# Squid_Leg_Controller.net
KiCad netlist of a schematic drawn in EAGLE
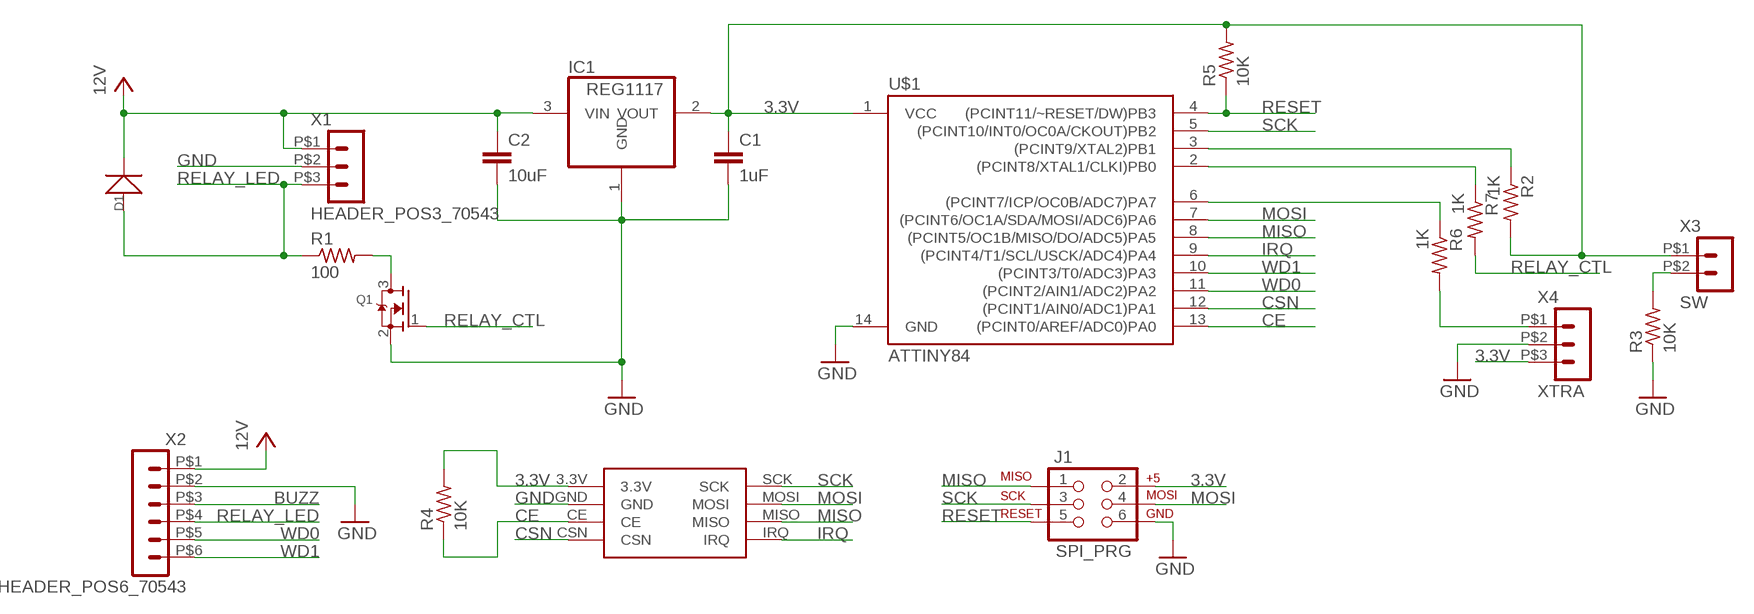
[diagram p0: schematic, sheet 1]

(export (version "E")
  (design (tool "Eeschema 10.0.6"))
  (components
    (comp (ref "C1")
      (value "1uF")
      (footprint "eagle-import:0805")
      (libsource (lib "eagle-import") (part "CAP0805"))
    )
    (comp (ref "C2")
      (value "10uF")
      (footprint "eagle-import:1206")
      (libsource (lib "eagle-import") (part "CAP1206"))
    )
    (comp (ref "D1")
      (value "D-SMA")
      (footprint "eagle-import:DO-214AC")
      (libsource (lib "eagle-import") (part "D-SMA"))
    )
    (comp (ref "IC1")
      (value "REG1117")
      (footprint "eagle-import:SOT223")
      (libsource (lib "eagle-import") (part "REG1117"))
    )
    (comp (ref "J1")
      (value "SPI_PRG")
      (footprint "eagle-import:2X3_LOCK")
      (libsource (lib "eagle-import") (part "AVR_SPI_PRG_62X3_LOCK"))
    )
    (comp (ref "Q1")
      (value "MOSFET-NREFLOW")
      (footprint "eagle-import:SOT23")
      (libsource (lib "eagle-import") (part "MOSFET-NREFLOW"))
    )
    (comp (ref "R1")
      (value "100")
      (footprint "eagle-import:R0603")
      (libsource (lib "eagle-import") (part "R-US_R0603"))
    )
    (comp (ref "R2")
      (value "1K")
      (footprint "eagle-import:R0603")
      (libsource (lib "eagle-import") (part "R-US_R0603"))
    )
    (comp (ref "R3")
      (value "10K")
      (footprint "eagle-import:R0603")
      (libsource (lib "eagle-import") (part "R-US_R0603"))
    )
    (comp (ref "R4")
      (value "10K")
      (footprint "eagle-import:R0603")
      (libsource (lib "eagle-import") (part "R-US_R0603"))
    )
    (comp (ref "R5")
      (value "10K")
      (footprint "eagle-import:R0603")
      (libsource (lib "eagle-import") (part "R-US_R0603"))
    )
    (comp (ref "R6")
      (value "1K")
      (footprint "eagle-import:R0603")
      (libsource (lib "eagle-import") (part "R-US_R0603"))
    )
    (comp (ref "R7")
      (value "1K")
      (footprint "eagle-import:R0603")
      (libsource (lib "eagle-import") (part "R-US_R0603"))
    )
    (comp (ref "U$1")
      (value "ATTINY84")
      (footprint "eagle-import:SO14")
      (libsource (lib "eagle-import") (part "ATTINY84"))
    )
    (comp (ref "U$4")
      (value "NRF24L01+")
      (footprint "eagle-import:NRF24L01+_MODULE_OFFBRD")
      (libsource (lib "eagle-import") (part "NRF24L01+_MODULEOFF_BOARD"))
    )
    (comp (ref "X1")
      (value "HEADER_POS3_70543")
      (footprint "eagle-import:70543-POS3")
      (libsource (lib "eagle-import") (part "HEADER_POS3_?70543"))
    )
    (comp (ref "X2")
      (value "HEADER_POS6_70543")
      (footprint "eagle-import:70543-POS6")
      (libsource (lib "eagle-import") (part "HEADER_POS6_?70543"))
    )
    (comp (ref "X3")
      (value "SW")
      (footprint "eagle-import:70543-POS2")
      (libsource (lib "eagle-import") (part "HEADER_POS2_?70543"))
    )
    (comp (ref "X4")
      (value "XTRA")
      (footprint "eagle-import:70543-POS3")
      (libsource (lib "eagle-import") (part "HEADER_POS3_?70543"))
    )
  )
  (nets
    (net (code "1") (name "/3.3V") (class "Default")
      (node (ref "C1") (pin "1") (pinfunction "1_1") (pintype "passive"))
      (node (ref "IC1") (pin "2") (pinfunction "VOUT_2") (pintype "output"))
      (node (ref "J1") (pin "2") (pinfunction "2_2") (pintype "passive"))
      (node (ref "R2") (pin "2") (pinfunction "2_2") (pintype "passive"))
      (node (ref "R4") (pin "2") (pinfunction "2_2") (pintype "passive"))
      (node (ref "R5") (pin "2") (pinfunction "2_2") (pintype "passive"))
      (node (ref "U$1") (pin "1") (pinfunction "VCC_1") (pintype "bidirectional"))
      (node (ref "U$4") (pin "3.3V") (pinfunction "3.3V_3.3V") (pintype "bidirectional"))
      (node (ref "X3") (pin "P$1") (pinfunction "1_P$1") (pintype "passive"))
      (node (ref "X4") (pin "P$3") (pinfunction "3_P$3") (pintype "passive"))
    )
    (net (code "2") (name "/BUZZ") (class "Default")
      (node (ref "X2") (pin "P$3") (pinfunction "3_P$3") (pintype "passive"))
    )
    (net (code "3") (name "/CE") (class "Default")
      (node (ref "R4") (pin "1") (pinfunction "1_1") (pintype "passive"))
      (node (ref "U$1") (pin "13") (pinfunction "(PCINT0/AREF/ADC0)PA0_13") (pintype "bidirectional"))
      (node (ref "U$4") (pin "CE") (pinfunction "CE_CE") (pintype "bidirectional"))
    )
    (net (code "4") (name "/CSN") (class "Default")
      (node (ref "U$1") (pin "12") (pinfunction "(PCINT1/AIN0/ADC1)PA1_12") (pintype "bidirectional"))
      (node (ref "U$4") (pin "CSN") (pinfunction "CSN_CSN") (pintype "bidirectional"))
    )
    (net (code "5") (name "/IRQ") (class "Default")
      (node (ref "U$1") (pin "9") (pinfunction "(PCINT4/T1/SCL/USCK/ADC4)PA4_9") (pintype "bidirectional"))
      (node (ref "U$4") (pin "IRQ") (pinfunction "IRQ_IRQ") (pintype "bidirectional"))
    )
    (net (code "6") (name "/MISO") (class "Default")
      (node (ref "J1") (pin "1") (pinfunction "1_1") (pintype "passive"))
      (node (ref "U$1") (pin "8") (pinfunction "(PCINT5/OC1B/MISO/DO/ADC5)PA5_8") (pintype "bidirectional"))
      (node (ref "U$4") (pin "MISO") (pinfunction "MISO_MISO") (pintype "bidirectional"))
    )
    (net (code "7") (name "/MOSI") (class "Default")
      (node (ref "J1") (pin "4") (pinfunction "4_4") (pintype "passive"))
      (node (ref "U$1") (pin "7") (pinfunction "(PCINT6/OC1A/SDA/MOSI/ADC6)PA6_7") (pintype "bidirectional"))
      (node (ref "U$4") (pin "MOSI") (pinfunction "MOSI_MOSI") (pintype "bidirectional"))
    )
    (net (code "8") (name "/RELAY_CTL") (class "Default")
      (node (ref "Q1") (pin "1") (pinfunction "G_1") (pintype "bidirectional"))
      (node (ref "R7") (pin "2") (pinfunction "2_2") (pintype "passive"))
    )
    (net (code "9") (name "/RELAY_LED") (class "Default")
      (node (ref "D1") (pin "1") (pinfunction "+_1") (pintype "passive"))
      (node (ref "R1") (pin "1") (pinfunction "1_1") (pintype "passive"))
      (node (ref "X1") (pin "P$3") (pinfunction "3_P$3") (pintype "passive"))
      (node (ref "X2") (pin "P$4") (pinfunction "4_P$4") (pintype "passive"))
    )
    (net (code "10") (name "/RESET") (class "Default")
      (node (ref "J1") (pin "5") (pinfunction "5_5") (pintype "passive"))
      (node (ref "R5") (pin "1") (pinfunction "1_1") (pintype "passive"))
      (node (ref "U$1") (pin "4") (pinfunction "(PCINT11/~{RESET/DW})PB3_4") (pintype "bidirectional"))
    )
    (net (code "11") (name "/SCK") (class "Default")
      (node (ref "J1") (pin "3") (pinfunction "3_3") (pintype "passive"))
      (node (ref "U$1") (pin "5") (pinfunction "(PCINT10/INT0/OC0A/CKOUT)PB2_5") (pintype "bidirectional"))
      (node (ref "U$4") (pin "SCK") (pinfunction "SCK_SCK") (pintype "bidirectional"))
    )
    (net (code "12") (name "/WD0") (class "Default")
      (node (ref "U$1") (pin "11") (pinfunction "(PCINT2/AIN1/ADC2)PA2_11") (pintype "bidirectional"))
      (node (ref "X2") (pin "P$5") (pinfunction "5_P$5") (pintype "passive"))
    )
    (net (code "13") (name "/WD1") (class "Default")
      (node (ref "U$1") (pin "10") (pinfunction "(PCINT3/T0/ADC3)PA3_10") (pintype "bidirectional"))
      (node (ref "X2") (pin "P$6") (pinfunction "6_P$6") (pintype "passive"))
    )
    (net (code "14") (name "12V") (class "Default")
      (node (ref "C2") (pin "1") (pinfunction "1_1") (pintype "passive"))
      (node (ref "D1") (pin "2") (pinfunction "-_2") (pintype "passive"))
      (node (ref "IC1") (pin "3") (pinfunction "VIN_3") (pintype "input"))
      (node (ref "X1") (pin "P$1") (pinfunction "1_P$1") (pintype "passive"))
      (node (ref "X2") (pin "P$1") (pinfunction "1_P$1") (pintype "passive"))
    )
    (net (code "15") (name "GND") (class "Default")
      (node (ref "C1") (pin "2") (pinfunction "2_2") (pintype "passive"))
      (node (ref "C2") (pin "2") (pinfunction "2_2") (pintype "passive"))
      (node (ref "IC1") (pin "1") (pinfunction "GND_1") (pintype "power_in"))
      (node (ref "J1") (pin "6") (pinfunction "6_6") (pintype "passive"))
      (node (ref "Q1") (pin "2") (pinfunction "S_2") (pintype "bidirectional"))
      (node (ref "R3") (pin "1") (pinfunction "1_1") (pintype "passive"))
      (node (ref "U$1") (pin "14") (pinfunction "GND_14") (pintype "bidirectional"))
      (node (ref "U$4") (pin "GND") (pinfunction "GND_GND") (pintype "bidirectional"))
      (node (ref "X1") (pin "P$2") (pinfunction "2_P$2") (pintype "passive"))
      (node (ref "X2") (pin "P$2") (pinfunction "2_P$2") (pintype "passive"))
      (node (ref "X4") (pin "P$2") (pinfunction "2_P$2") (pintype "passive"))
    )
    (net (code "16") (name "Net-(Q1-D)") (class "Default")
      (node (ref "Q1") (pin "3") (pinfunction "D_3") (pintype "bidirectional"))
      (node (ref "R1") (pin "2") (pinfunction "2_2") (pintype "passive"))
    )
    (net (code "17") (name "Net-(U$1-(PCINT7{slash}ICP{slash}OC0B{slash}ADC7)PA7)") (class "Default")
      (node (ref "R6") (pin "1") (pinfunction "1_1") (pintype "passive"))
      (node (ref "U$1") (pin "6") (pinfunction "(PCINT7/ICP/OC0B/ADC7)PA7_6") (pintype "bidirectional"))
    )
    (net (code "18") (name "Net-(U$1-(PCINT8{slash}XTAL1{slash}CLKI)PB0)") (class "Default")
      (node (ref "R7") (pin "1") (pinfunction "1_1") (pintype "passive"))
      (node (ref "U$1") (pin "2") (pinfunction "(PCINT8/XTAL1/CLKI)PB0_2") (pintype "bidirectional"))
    )
    (net (code "19") (name "Net-(U$1-(PCINT9{slash}XTAL2)PB1)") (class "Default")
      (node (ref "R2") (pin "1") (pinfunction "1_1") (pintype "passive"))
      (node (ref "U$1") (pin "3") (pinfunction "(PCINT9/XTAL2)PB1_3") (pintype "bidirectional"))
    )
    (net (code "20") (name "Net-(X3-2)") (class "Default")
      (node (ref "R3") (pin "2") (pinfunction "2_2") (pintype "passive"))
      (node (ref "X3") (pin "P$2") (pinfunction "2_P$2") (pintype "passive"))
    )
    (net (code "21") (name "Net-(X4-1)") (class "Default")
      (node (ref "R6") (pin "2") (pinfunction "2_2") (pintype "passive"))
      (node (ref "X4") (pin "P$1") (pinfunction "1_P$1") (pintype "passive"))
    )
  )
)
